# Sheet1.net
KiCad netlist of a schematic drawn in Altium Designer
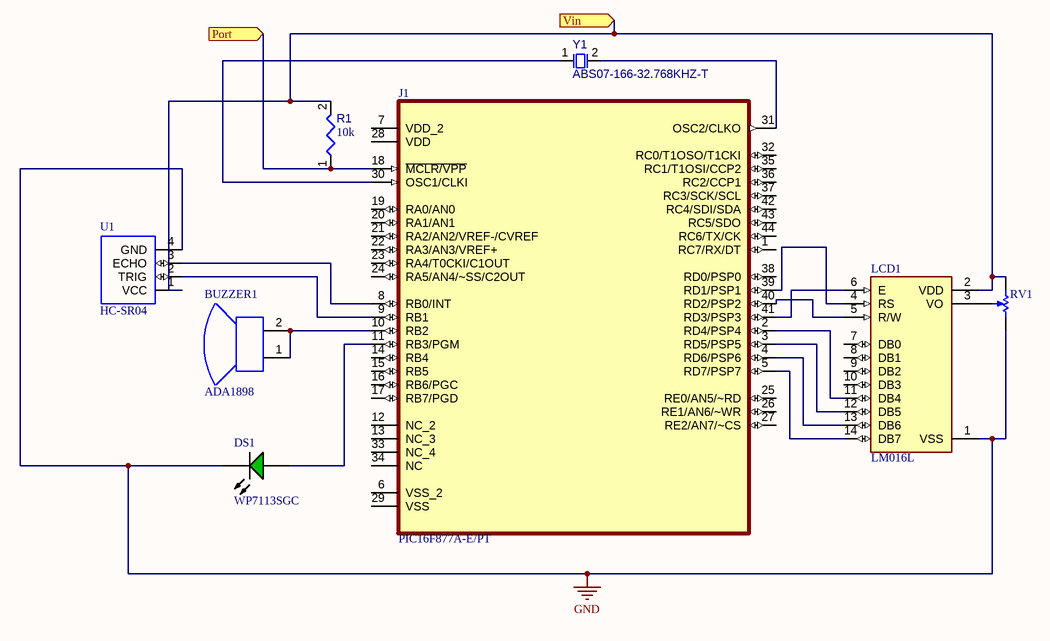
[diagram p0: Sheet1.SchDoc]

(export (version "E")
  (design (tool "Eeschema 10.0.6"))
  (components
    (comp (ref "BUZZER1")
      (value "ADA1898")
      (footprint "ADAI-ADA1898")
      (description "Mini Speaker, 8 Ohm, 0.2 Wmax, -10 to 40 degC, 2-Pin THD, RoHS")
      (fields (field (name "MANUFACTURER") "Adafruit Industries"))
      (libsource (lib "Lê Nguyên") (part "SPEAKER-2"))
    )
    (comp (ref "DS1")
      (value "WP7113SGC")
      (footprint "KING-WP7113SGC_V")
      (description "The Super Bright Green Source Color Device, 2.2 V, -40 to 85 degC, 2-Pin THD, RoHS, Tape and Reel")
      (fields (field (name "MANUFACTURER") "Kingbright"))
      (libsource (lib "Lê Nguyên") (part "LED-GREEN-AK-2"))
    )
    (comp (ref "J1")
      (value "PIC16F877A-E/PT")
      (footprint "QFP80P1200X1200X120-44N")
      (description "7 KB Flash, 368 RAM, 33 I/O44 TQFP 10x10x1mm TRAY ¦ Microchip Technology Inc. PIC16F877A-E/PT")
      (fields (field (name "MF") "Microchip"))
      (libsource (lib "PIC16F877A-E_PT") (part "PIC16F877A-E/PT"))
    )
    (comp (ref "LCD1")
      (value "LM016L")
      (footprint "LCD_LM016L")
      (description "Display Lcd 35x75mm")
      (fields (field (name "MF") "Hitachi"))
      (libsource (lib "LM016L") (part "LM016L"))
    )
    (comp (ref "R1")
      (value "10k")
      (footprint "RESC3216X60X45ML15T20")
      (description "Chip Resistor, 10 KOhm, +/- 1%, 0.25 W, -55 to 155 degC, 1206 (3216 Metric)")
      (fields (field (name "TOLERANCE") "1%") (field (name "POWER") "250mW"))
      (libsource (lib "Lê Nguyên") (part "RES-2"))
    )
    (comp (ref "RV1")
      (value "TC33X-2-103E")
      (footprint "BOUR-TC33X-2_V")
      (description "Trimming Potentiometer, 1000 Ohm, -40 to 100 degC, 3-Pin SMD, RoHS, Tape and Reel")
      (fields (field (name "TOLERANCE") "25%") (field (name "POWER") "100mW"))
      (libsource (lib "Lê Nguyên") (part "RES-ADJ-3_A"))
    )
    (comp (ref "U1")
      (value "HC-SR04")
      (footprint "XCVR_HC-SR04")
      (description "Ultrasonic Sensor Module")
      (libsource (lib "HC-SR04") (part "HC-SR04"))
    )
    (comp (ref "Y1")
      (value "ABS07-166-32.768KHZ-T")
      (footprint "EPSON-FC-135_V")
      (description "Crystal 32.768kHz 10ppm 7pF -40C +85C")
      (libsource (lib "Lê Nguyên") (part "CMP-001-0024-1"))
    )
  )
  (nets
    (net (code "1") (name "/Port") (class "Default")
      (node (ref "J1") (pin "18") (pinfunction "~{MCLR/VPP}_18") (pintype "input"))
      (node (ref "R1") (pin "1") (pinfunction "1_1") (pintype "passive"))
    )
    (net (code "2") (name "/Vin") (class "Default")
      (node (ref "LCD1") (pin "2") (pinfunction "VDD_2") (pintype "power_in"))
      (node (ref "R1") (pin "2") (pinfunction "2_2") (pintype "passive"))
      (node (ref "RV1") (pin "1") (pinfunction "1_1") (pintype "passive"))
      (node (ref "U1") (pin "1") (pinfunction "VCC_1") (pintype "power_in"))
    )
    (net (code "3") (name "GND") (class "Default")
      (node (ref "DS1") (pin "2") (pinfunction "K_2") (pintype "passive"))
      (node (ref "LCD1") (pin "1") (pinfunction "VSS_1") (pintype "power_in"))
      (node (ref "RV1") (pin "3") (pinfunction "3_3") (pintype "passive"))
      (node (ref "U1") (pin "4") (pinfunction "GND_4") (pintype "power_in"))
    )
    (net (code "4") (name "Net-(BUZZER1-+)") (class "Default")
      (node (ref "BUZZER1") (pin "1") (pinfunction "+_1") (pintype "passive"))
      (node (ref "BUZZER1") (pin "2") (pinfunction "-_2") (pintype "passive"))
      (node (ref "J1") (pin "10") (pinfunction "RB2_10") (pintype "bidirectional"))
    )
    (net (code "5") (name "Net-(DS1-A)") (class "Default")
      (node (ref "DS1") (pin "1") (pinfunction "A_1") (pintype "passive"))
      (node (ref "J1") (pin "11") (pinfunction "RB3/PGM_11") (pintype "bidirectional"))
    )
    (net (code "6") (name "Net-(J1-OSC1{slash}CLKI)") (class "Default")
      (node (ref "J1") (pin "30") (pinfunction "OSC1/CLKI_30") (pintype "input"))
      (node (ref "Y1") (pin "1") (pinfunction "1_1") (pintype "passive"))
    )
    (net (code "7") (name "Net-(J1-OSC2{slash}CLKO)") (class "Default")
      (node (ref "J1") (pin "31") (pinfunction "OSC2/CLKO_31") (pintype "output"))
      (node (ref "Y1") (pin "2") (pinfunction "2_2") (pintype "passive"))
    )
    (net (code "8") (name "Net-(J1-RB0{slash}INT)") (class "Default")
      (node (ref "J1") (pin "8") (pinfunction "RB0/INT_8") (pintype "bidirectional"))
      (node (ref "U1") (pin "3") (pinfunction "ECHO_3") (pintype "bidirectional"))
    )
    (net (code "9") (name "Net-(J1-RB1)") (class "Default")
      (node (ref "J1") (pin "9") (pinfunction "RB1_9") (pintype "bidirectional"))
      (node (ref "U1") (pin "2") (pinfunction "TRIG_2") (pintype "bidirectional"))
    )
    (net (code "10") (name "Net-(J1-RD1{slash}PSP1)") (class "Default")
      (node (ref "J1") (pin "39") (pinfunction "RD1/PSP1_39") (pintype "bidirectional"))
      (node (ref "LCD1") (pin "4") (pinfunction "RS_4") (pintype "input"))
    )
    (net (code "11") (name "Net-(J1-RD2{slash}PSP2)") (class "Default")
      (node (ref "J1") (pin "40") (pinfunction "RD2/PSP2_40") (pintype "bidirectional"))
      (node (ref "LCD1") (pin "5") (pinfunction "R/W_5") (pintype "input"))
    )
    (net (code "12") (name "Net-(J1-RD3{slash}PSP3)") (class "Default")
      (node (ref "J1") (pin "41") (pinfunction "RD3/PSP3_41") (pintype "bidirectional"))
      (node (ref "LCD1") (pin "6") (pinfunction "E_6") (pintype "input"))
    )
    (net (code "13") (name "Net-(J1-RD4{slash}PSP4)") (class "Default")
      (node (ref "J1") (pin "2") (pinfunction "RD4/PSP4_2") (pintype "bidirectional"))
      (node (ref "LCD1") (pin "11") (pinfunction "DB4_11") (pintype "bidirectional"))
    )
    (net (code "14") (name "Net-(J1-RD5{slash}PSP5)") (class "Default")
      (node (ref "J1") (pin "3") (pinfunction "RD5/PSP5_3") (pintype "bidirectional"))
      (node (ref "LCD1") (pin "12") (pinfunction "DB5_12") (pintype "bidirectional"))
    )
    (net (code "15") (name "Net-(J1-RD6{slash}PSP6)") (class "Default")
      (node (ref "J1") (pin "4") (pinfunction "RD6/PSP6_4") (pintype "bidirectional"))
      (node (ref "LCD1") (pin "13") (pinfunction "DB6_13") (pintype "bidirectional"))
    )
    (net (code "16") (name "Net-(J1-RD7{slash}PSP7)") (class "Default")
      (node (ref "J1") (pin "5") (pinfunction "RD7/PSP7_5") (pintype "bidirectional"))
      (node (ref "LCD1") (pin "14") (pinfunction "DB7_14") (pintype "bidirectional"))
    )
    (net (code "17") (name "Net-(LCD1-VO)") (class "Default")
      (node (ref "LCD1") (pin "3") (pinfunction "VO_3") (pintype "power_in"))
      (node (ref "RV1") (pin "2") (pinfunction "2_2") (pintype "passive"))
    )
    (net (code "18") (name "unconnected-(J1-NC-Pad34)") (class "Default")
      (node (ref "J1") (pin "34") (pinfunction "NC_34") (pintype "passive"))
    )
    (net (code "19") (name "unconnected-(J1-NC_2-Pad12)") (class "Default")
      (node (ref "J1") (pin "12") (pinfunction "NC_2_12") (pintype "passive"))
    )
    (net (code "20") (name "unconnected-(J1-NC_3-Pad13)") (class "Default")
      (node (ref "J1") (pin "13") (pinfunction "NC_3_13") (pintype "passive"))
    )
    (net (code "21") (name "unconnected-(J1-NC_4-Pad33)") (class "Default")
      (node (ref "J1") (pin "33") (pinfunction "NC_4_33") (pintype "passive"))
    )
    (net (code "22") (name "unconnected-(J1-RA0{slash}AN0-Pad19)") (class "Default")
      (node (ref "J1") (pin "19") (pinfunction "RA0/AN0_19") (pintype "bidirectional"))
    )
    (net (code "23") (name "unconnected-(J1-RA1{slash}AN1-Pad20)") (class "Default")
      (node (ref "J1") (pin "20") (pinfunction "RA1/AN1_20") (pintype "bidirectional"))
    )
    (net (code "24") (name "unconnected-(J1-RA2{slash}AN2{slash}VREF-{slash}CVREF-Pad21)") (class "Default")
      (node (ref "J1") (pin "21") (pinfunction "RA2/AN2/VREF-/CVREF_21") (pintype "bidirectional"))
    )
    (net (code "25") (name "unconnected-(J1-RA3{slash}AN3{slash}VREF+-Pad22)") (class "Default")
      (node (ref "J1") (pin "22") (pinfunction "RA3/AN3/VREF+_22") (pintype "bidirectional"))
    )
    (net (code "26") (name "unconnected-(J1-RA4{slash}T0CKI{slash}C1OUT-Pad23)") (class "Default")
      (node (ref "J1") (pin "23") (pinfunction "RA4/T0CKI/C1OUT_23") (pintype "bidirectional"))
    )
    (net (code "27") (name "unconnected-(J1-RA5{slash}AN4{slash}~SS{slash}C2OUT-Pad24)") (class "Default")
      (node (ref "J1") (pin "24") (pinfunction "RA5/AN4/~SS/C2OUT_24") (pintype "bidirectional"))
    )
    (net (code "28") (name "unconnected-(J1-RB4-Pad14)") (class "Default")
      (node (ref "J1") (pin "14") (pinfunction "RB4_14") (pintype "bidirectional"))
    )
    (net (code "29") (name "unconnected-(J1-RB5-Pad15)") (class "Default")
      (node (ref "J1") (pin "15") (pinfunction "RB5_15") (pintype "bidirectional"))
    )
    (net (code "30") (name "unconnected-(J1-RB6{slash}PGC-Pad16)") (class "Default")
      (node (ref "J1") (pin "16") (pinfunction "RB6/PGC_16") (pintype "bidirectional"))
    )
    (net (code "31") (name "unconnected-(J1-RB7{slash}PGD-Pad17)") (class "Default")
      (node (ref "J1") (pin "17") (pinfunction "RB7/PGD_17") (pintype "bidirectional"))
    )
    (net (code "32") (name "unconnected-(J1-RC0{slash}T1OSO{slash}T1CKI-Pad32)") (class "Default")
      (node (ref "J1") (pin "32") (pinfunction "RC0/T1OSO/T1CKI_32") (pintype "bidirectional"))
    )
    (net (code "33") (name "unconnected-(J1-RC1{slash}T1OSI{slash}CCP2-Pad35)") (class "Default")
      (node (ref "J1") (pin "35") (pinfunction "RC1/T1OSI/CCP2_35") (pintype "bidirectional"))
    )
    (net (code "34") (name "unconnected-(J1-RC2{slash}CCP1-Pad36)") (class "Default")
      (node (ref "J1") (pin "36") (pinfunction "RC2/CCP1_36") (pintype "bidirectional"))
    )
    (net (code "35") (name "unconnected-(J1-RC3{slash}SCK{slash}SCL-Pad37)") (class "Default")
      (node (ref "J1") (pin "37") (pinfunction "RC3/SCK/SCL_37") (pintype "bidirectional"))
    )
    (net (code "36") (name "unconnected-(J1-RC4{slash}SDI{slash}SDA-Pad42)") (class "Default")
      (node (ref "J1") (pin "42") (pinfunction "RC4/SDI/SDA_42") (pintype "bidirectional"))
    )
    (net (code "37") (name "unconnected-(J1-RC5{slash}SDO-Pad43)") (class "Default")
      (node (ref "J1") (pin "43") (pinfunction "RC5/SDO_43") (pintype "bidirectional"))
    )
    (net (code "38") (name "unconnected-(J1-RC6{slash}TX{slash}CK-Pad44)") (class "Default")
      (node (ref "J1") (pin "44") (pinfunction "RC6/TX/CK_44") (pintype "bidirectional"))
    )
    (net (code "39") (name "unconnected-(J1-RC7{slash}RX{slash}DT-Pad1)") (class "Default")
      (node (ref "J1") (pin "1") (pinfunction "RC7/RX/DT_1") (pintype "bidirectional"))
    )
    (net (code "40") (name "unconnected-(J1-RD0{slash}PSP0-Pad38)") (class "Default")
      (node (ref "J1") (pin "38") (pinfunction "RD0/PSP0_38") (pintype "bidirectional"))
    )
    (net (code "41") (name "unconnected-(J1-RE0{slash}AN5{slash}~RD-Pad25)") (class "Default")
      (node (ref "J1") (pin "25") (pinfunction "RE0/AN5/~RD_25") (pintype "bidirectional"))
    )
    (net (code "42") (name "unconnected-(J1-RE1{slash}AN6{slash}~WR-Pad26)") (class "Default")
      (node (ref "J1") (pin "26") (pinfunction "RE1/AN6/~WR_26") (pintype "bidirectional"))
    )
    (net (code "43") (name "unconnected-(J1-RE2{slash}AN7{slash}~CS-Pad27)") (class "Default")
      (node (ref "J1") (pin "27") (pinfunction "RE2/AN7/~CS_27") (pintype "bidirectional"))
    )
    (net (code "44") (name "unconnected-(J1-VDD-Pad28)") (class "Default")
      (node (ref "J1") (pin "28") (pinfunction "VDD_28") (pintype "power_in"))
    )
    (net (code "45") (name "unconnected-(J1-VDD_2-Pad7)") (class "Default")
      (node (ref "J1") (pin "7") (pinfunction "VDD_2_7") (pintype "power_in"))
    )
    (net (code "46") (name "unconnected-(J1-VSS-Pad29)") (class "Default")
      (node (ref "J1") (pin "29") (pinfunction "VSS_29") (pintype "power_in"))
    )
    (net (code "47") (name "unconnected-(J1-VSS_2-Pad6)") (class "Default")
      (node (ref "J1") (pin "6") (pinfunction "VSS_2_6") (pintype "power_in"))
    )
    (net (code "48") (name "unconnected-(LCD1-DB0-Pad7)") (class "Default")
      (node (ref "LCD1") (pin "7") (pinfunction "DB0_7") (pintype "bidirectional"))
    )
    (net (code "49") (name "unconnected-(LCD1-DB1-Pad8)") (class "Default")
      (node (ref "LCD1") (pin "8") (pinfunction "DB1_8") (pintype "bidirectional"))
    )
    (net (code "50") (name "unconnected-(LCD1-DB2-Pad9)") (class "Default")
      (node (ref "LCD1") (pin "9") (pinfunction "DB2_9") (pintype "bidirectional"))
    )
    (net (code "51") (name "unconnected-(LCD1-DB3-Pad10)") (class "Default")
      (node (ref "LCD1") (pin "10") (pinfunction "DB3_10") (pintype "bidirectional"))
    )
  )
)
